# LED_indicators.net
KiCad netlist of a schematic drawn in Altium Designer
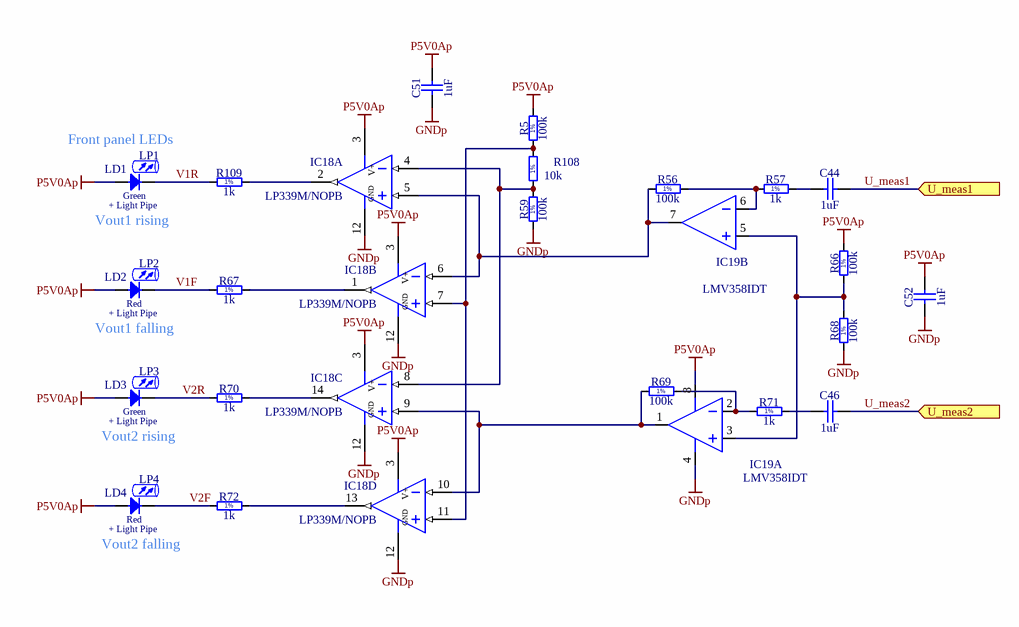
[diagram p0: LED_indicators.SchDoc]

(export (version "E")
  (design (tool "Eeschema 10.0.6"))
  (components
    (comp (ref "C44")
      (value "1uF")
      (footprint "CAPC1005X55N")
      (description "Non-polarised capacitor")
      (fields
        (field (name "PART NUMBER") "CC0402_1UF_16V_10%_X5R")
        (field (name "VOLTAGE") "16V")
        (field (name "AUTHOR") "CERN DEM JLC")
      )
      (libsource (lib "Capacitors") (part "Capacitor - non polarized"))
    )
    (comp (ref "C46")
      (value "1uF")
      (footprint "CAPC1005X55N")
      (description "Non-polarised capacitor")
      (fields
        (field (name "PART NUMBER") "CC0402_1UF_16V_10%_X5R")
        (field (name "VOLTAGE") "16V")
        (field (name "AUTHOR") "CERN DEM JLC")
      )
      (libsource (lib "Capacitors") (part "Capacitor - non polarized"))
    )
    (comp (ref "C51")
      (value "1uF")
      (footprint "CAPC1005X55N")
      (description "Non-polarised capacitor")
      (fields
        (field (name "PART NUMBER") "CC0402_1UF_16V_10%_X5R")
        (field (name "VOLTAGE") "16V")
        (field (name "AUTHOR") "CERN DEM JLC")
      )
      (libsource (lib "Capacitors") (part "Capacitor - non polarized"))
    )
    (comp (ref "C52")
      (value "1uF")
      (footprint "CAPC1005X55N")
      (description "Non-polarised capacitor")
      (fields
        (field (name "PART NUMBER") "CC0402_1UF_16V_10%_X5R")
        (field (name "VOLTAGE") "16V")
        (field (name "AUTHOR") "CERN DEM JLC")
      )
      (libsource (lib "Capacitors") (part "Capacitor - non polarized"))
    )
    (comp (ref "IC18")
      (value "LP339M/NOPB")
      (footprint "SOIC127P600X175-14N")
      (description "Quad Operational Amplifier")
      (fields (field (name "MANUFACTURER") "TEXAS INSTRUMENTS") (field (name "AUTHOR") "CERN DEM MR"))
      (libsource (lib "ICs And Semiconductors") (part "Operational Amplifier x4 Type5"))
    )
    (comp (ref "IC19")
      (value "LMV358IDT")
      (footprint "SO-8")
      (description "Low voltage, Rail-to_Rail output Operational Amplifier")
      (libsource (lib "Amplifiers") (part "OA_LMV358"))
    )
    (comp (ref "LD1")
      (value "Green")
      (footprint "LED_DIALIGHT_555-230")
      (description "LED Green 1C 2A")
      (fields
        (field (name "PART NUMBER") "LED_DIALIGHT_555-2301F")
        (field (name "MANUFACTURER") "DIALIGHT")
        (field (name "AUTHOR") "CERN DEM JMW")
      )
      (libsource (lib "ICs And Semiconductors") (part "LED Green 1C 2A"))
    )
    (comp (ref "LD2")
      (value "Red")
      (footprint "LED_DIALIGHT_555-200")
      (description "LED Red 1C 2A")
      (fields
        (field (name "PART NUMBER") "LED_DIALIGHT_555-2001F")
        (field (name "MANUFACTURER") "DIALIGHT")
        (field (name "AUTHOR") "CERN DEM JMW")
      )
      (libsource (lib "ICs And Semiconductors") (part "LED Red 1C 2A"))
    )
    (comp (ref "LD3")
      (value "Green")
      (footprint "LED_DIALIGHT_555-230")
      (description "LED Green 1C 2A")
      (fields
        (field (name "PART NUMBER") "LED_DIALIGHT_555-2301F")
        (field (name "MANUFACTURER") "DIALIGHT")
        (field (name "AUTHOR") "CERN DEM JMW")
      )
      (libsource (lib "ICs And Semiconductors") (part "LED Green 1C 2A"))
    )
    (comp (ref "LD4")
      (value "Red")
      (footprint "LED_DIALIGHT_555-200")
      (description "LED Red 1C 2A")
      (fields
        (field (name "PART NUMBER") "LED_DIALIGHT_555-2001F")
        (field (name "MANUFACTURER") "DIALIGHT")
        (field (name "AUTHOR") "CERN DEM JMW")
      )
      (libsource (lib "ICs And Semiconductors") (part "LED Red 1C 2A"))
    )
    (comp (ref "LP1")
      (value "~")
      (footprint "LEDLP_BIVAR_PLP2-1200")
      (description "LED Light Pipe x1 Type1")
      (fields
        (field (name "PART NUMBER") "LEDLP_BIVAR_PLP2-1200")
        (field (name "MANUFACTURER") "BIVAR")
        (field (name "AUTHOR") "CERN DEM HF")
      )
      (libsource (lib "ICs And Semiconductors") (part "LED Light Pipe x1 Type1"))
    )
    (comp (ref "LP2")
      (value "~")
      (footprint "LEDLP_BIVAR_PLP2-1200")
      (description "LED Light Pipe x1 Type1")
      (fields
        (field (name "PART NUMBER") "LEDLP_BIVAR_PLP2-1200")
        (field (name "MANUFACTURER") "BIVAR")
        (field (name "AUTHOR") "CERN DEM HF")
      )
      (libsource (lib "ICs And Semiconductors") (part "LED Light Pipe x1 Type1"))
    )
    (comp (ref "LP3")
      (value "~")
      (footprint "LEDLP_BIVAR_PLP2-1200")
      (description "LED Light Pipe x1 Type1")
      (fields
        (field (name "PART NUMBER") "LEDLP_BIVAR_PLP2-1200")
        (field (name "MANUFACTURER") "BIVAR")
        (field (name "AUTHOR") "CERN DEM HF")
      )
      (libsource (lib "ICs And Semiconductors") (part "LED Light Pipe x1 Type1"))
    )
    (comp (ref "LP4")
      (value "~")
      (footprint "LEDLP_BIVAR_PLP2-1200")
      (description "LED Light Pipe x1 Type1")
      (fields
        (field (name "PART NUMBER") "LEDLP_BIVAR_PLP2-1200")
        (field (name "MANUFACTURER") "BIVAR")
        (field (name "AUTHOR") "CERN DEM HF")
      )
      (libsource (lib "ICs And Semiconductors") (part "LED Light Pipe x1 Type1"))
    )
    (comp (ref "R5")
      (value "100k")
      (footprint "RESC1608X55N")
      (description "Resistor - 1%")
      (fields
        (field (name "PART NUMBER") "R0603_100K_1%_0.1W_100PPM")
        (field (name "POWER") "0.1W")
        (field (name "AUTHOR") "CERN DEM JLC")
      )
      (libsource (lib "Resistors") (part "Resistor - 1%"))
    )
    (comp (ref "R56")
      (value "100k")
      (footprint "RESC1608X55N")
      (description "Resistor - 1%")
      (fields
        (field (name "PART NUMBER") "R0603_100K_1%_0.1W_100PPM")
        (field (name "POWER") "0.1W")
        (field (name "AUTHOR") "CERN DEM JLC")
      )
      (libsource (lib "Resistors") (part "Resistor - 1%"))
    )
    (comp (ref "R57")
      (value "1k")
      (footprint "RESC1005X40N")
      (description "Resistor - 1%")
      (fields
        (field (name "PART NUMBER") "R0402_1K_1%_0.0625W_100PPM")
        (field (name "POWER") "0.0625W")
        (field (name "AUTHOR") "CERN DEM JLC")
      )
      (libsource (lib "Resistors") (part "Resistor - 1%"))
    )
    (comp (ref "R59")
      (value "100k")
      (footprint "RESC1608X55N")
      (description "Resistor - 1%")
      (fields
        (field (name "PART NUMBER") "R0603_100K_1%_0.1W_100PPM")
        (field (name "POWER") "0.1W")
        (field (name "AUTHOR") "CERN DEM JLC")
      )
      (libsource (lib "Resistors") (part "Resistor - 1%"))
    )
    (comp (ref "R66")
      (value "100k")
      (footprint "RESC1608X55N")
      (description "Resistor - 1%")
      (fields
        (field (name "PART NUMBER") "R0603_100K_1%_0.1W_100PPM")
        (field (name "POWER") "0.1W")
        (field (name "AUTHOR") "CERN DEM JLC")
      )
      (libsource (lib "Resistors") (part "Resistor - 1%"))
    )
    (comp (ref "R67")
      (value "1k")
      (footprint "RESC1005X40N")
      (description "Resistor - 1%")
      (fields
        (field (name "PART NUMBER") "R0402_1K_1%_0.0625W_100PPM")
        (field (name "POWER") "0.0625W")
        (field (name "AUTHOR") "CERN DEM JLC")
      )
      (libsource (lib "Resistors") (part "Resistor - 1%"))
    )
    (comp (ref "R68")
      (value "100k")
      (footprint "RESC1608X55N")
      (description "Resistor - 1%")
      (fields
        (field (name "PART NUMBER") "R0603_100K_1%_0.1W_100PPM")
        (field (name "POWER") "0.1W")
        (field (name "AUTHOR") "CERN DEM JLC")
      )
      (libsource (lib "Resistors") (part "Resistor - 1%"))
    )
    (comp (ref "R69")
      (value "100k")
      (footprint "RESC1608X55N")
      (description "Resistor - 1%")
      (fields
        (field (name "PART NUMBER") "R0603_100K_1%_0.1W_100PPM")
        (field (name "POWER") "0.1W")
        (field (name "AUTHOR") "CERN DEM JLC")
      )
      (libsource (lib "Resistors") (part "Resistor - 1%"))
    )
    (comp (ref "R70")
      (value "1k")
      (footprint "RESC1005X40N")
      (description "Resistor - 1%")
      (fields
        (field (name "PART NUMBER") "R0402_1K_1%_0.0625W_100PPM")
        (field (name "POWER") "0.0625W")
        (field (name "AUTHOR") "CERN DEM JLC")
      )
      (libsource (lib "Resistors") (part "Resistor - 1%"))
    )
    (comp (ref "R71")
      (value "1k")
      (footprint "RESC1005X40N")
      (description "Resistor - 1%")
      (fields
        (field (name "PART NUMBER") "R0402_1K_1%_0.0625W_100PPM")
        (field (name "POWER") "0.0625W")
        (field (name "AUTHOR") "CERN DEM JLC")
      )
      (libsource (lib "Resistors") (part "Resistor - 1%"))
    )
    (comp (ref "R72")
      (value "1k")
      (footprint "RESC1005X40N")
      (description "Resistor - 1%")
      (fields
        (field (name "PART NUMBER") "R0402_1K_1%_0.0625W_100PPM")
        (field (name "POWER") "0.0625W")
        (field (name "AUTHOR") "CERN DEM JLC")
      )
      (libsource (lib "Resistors") (part "Resistor - 1%"))
    )
    (comp (ref "R108")
      (value "10k")
      (footprint "RESC1005X40N")
      (description "Resistor - 1%")
      (fields
        (field (name "PART NUMBER") "R0402_10K_1%_0.0625W_100PPM")
        (field (name "POWER") "0.0625W")
        (field (name "AUTHOR") "CERN DEM JLC")
      )
      (libsource (lib "Resistors") (part "Resistor - 1%"))
    )
    (comp (ref "R109")
      (value "1k")
      (footprint "RESC1005X40N")
      (description "Resistor - 1%")
      (fields
        (field (name "PART NUMBER") "R0402_1K_1%_0.0625W_100PPM")
        (field (name "POWER") "0.0625W")
        (field (name "AUTHOR") "CERN DEM JLC")
      )
      (libsource (lib "Resistors") (part "Resistor - 1%"))
    )
  )
  (nets
    (net (code "1") (name "/U_meas1") (class "Default")
      (node (ref "C44") (pin "2") (pinfunction "2_2") (pintype "passive"))
    )
    (net (code "2") (name "/U_meas2") (class "Default")
      (node (ref "C46") (pin "2") (pinfunction "2_2") (pintype "passive"))
    )
    (net (code "3") (name "/V1F") (class "Default")
      (node (ref "LD2") (pin "1") (pinfunction "C_1") (pintype "passive"))
      (node (ref "R67") (pin "1") (pinfunction "1_1") (pintype "passive"))
    )
    (net (code "4") (name "/V1R") (class "Default")
      (node (ref "LD1") (pin "1") (pinfunction "C_1") (pintype "passive"))
      (node (ref "R109") (pin "1") (pinfunction "1_1") (pintype "passive"))
    )
    (net (code "5") (name "/V2F") (class "Default")
      (node (ref "LD4") (pin "1") (pinfunction "C_1") (pintype "passive"))
      (node (ref "R72") (pin "1") (pinfunction "1_1") (pintype "passive"))
    )
    (net (code "6") (name "/V2R") (class "Default")
      (node (ref "LD3") (pin "1") (pinfunction "C_1") (pintype "passive"))
      (node (ref "R70") (pin "1") (pinfunction "1_1") (pintype "passive"))
    )
    (net (code "7") (name "GNDp") (class "Default")
      (node (ref "C51") (pin "1") (pinfunction "1_1") (pintype "passive"))
      (node (ref "C52") (pin "1") (pinfunction "1_1") (pintype "passive"))
      (node (ref "IC18") (pin "12") (pinfunction "GND_12") (pintype "power_in"))
      (node (ref "IC19") (pin "4") (pinfunction "V-_4") (pintype "passive"))
      (node (ref "R59") (pin "1") (pinfunction "1_1") (pintype "passive"))
      (node (ref "R68") (pin "1") (pinfunction "1_1") (pintype "passive"))
    )
    (net (code "8") (name "Net-(C44-Pad1)") (class "Default")
      (node (ref "C44") (pin "1") (pinfunction "1_1") (pintype "passive"))
      (node (ref "R57") (pin "2") (pinfunction "2_2") (pintype "passive"))
    )
    (net (code "9") (name "Net-(C46-Pad1)") (class "Default")
      (node (ref "C46") (pin "1") (pinfunction "1_1") (pintype "passive"))
      (node (ref "R71") (pin "2") (pinfunction "2_2") (pintype "passive"))
    )
    (net (code "10") (name "Net-(IC18A-IN+)") (class "Default")
      (node (ref "IC18") (pin "5") (pinfunction "IN+_5") (pintype "input"))
      (node (ref "IC18") (pin "6") (pinfunction "IN-_6") (pintype "input"))
      (node (ref "IC19") (pin "7") (pinfunction "OUT_7") (pintype "passive"))
      (node (ref "R56") (pin "1") (pinfunction "1_1") (pintype "passive"))
    )
    (net (code "11") (name "Net-(IC18A-IN-)") (class "Default")
      (node (ref "IC18") (pin "4") (pinfunction "IN-_4") (pintype "input"))
      (node (ref "IC18") (pin "8") (pinfunction "IN-_8") (pintype "input"))
      (node (ref "R108") (pin "1") (pinfunction "1_1") (pintype "passive"))
      (node (ref "R59") (pin "2") (pinfunction "2_2") (pintype "passive"))
    )
    (net (code "12") (name "Net-(IC18A-OUT)") (class "Default")
      (node (ref "IC18") (pin "2") (pinfunction "OUT_2") (pintype "output"))
      (node (ref "R109") (pin "2") (pinfunction "2_2") (pintype "passive"))
    )
    (net (code "13") (name "Net-(IC18B-IN+)") (class "Default")
      (node (ref "IC18") (pin "11") (pinfunction "IN+_11") (pintype "input"))
      (node (ref "IC18") (pin "7") (pinfunction "IN+_7") (pintype "input"))
      (node (ref "R108") (pin "2") (pinfunction "2_2") (pintype "passive"))
      (node (ref "R5") (pin "1") (pinfunction "1_1") (pintype "passive"))
    )
    (net (code "14") (name "Net-(IC18B-OUT)") (class "Default")
      (node (ref "IC18") (pin "1") (pinfunction "OUT_1") (pintype "output"))
      (node (ref "R67") (pin "2") (pinfunction "2_2") (pintype "passive"))
    )
    (net (code "15") (name "Net-(IC18C-IN+)") (class "Default")
      (node (ref "IC18") (pin "10") (pinfunction "IN-_10") (pintype "input"))
      (node (ref "IC18") (pin "9") (pinfunction "IN+_9") (pintype "input"))
      (node (ref "IC19") (pin "1") (pinfunction "OUT_1") (pintype "passive"))
      (node (ref "R69") (pin "1") (pinfunction "1_1") (pintype "passive"))
    )
    (net (code "16") (name "Net-(IC18C-OUT)") (class "Default")
      (node (ref "IC18") (pin "14") (pinfunction "OUT_14") (pintype "output"))
      (node (ref "R70") (pin "2") (pinfunction "2_2") (pintype "passive"))
    )
    (net (code "17") (name "Net-(IC18D-OUT)") (class "Default")
      (node (ref "IC18") (pin "13") (pinfunction "OUT_13") (pintype "output"))
      (node (ref "R72") (pin "2") (pinfunction "2_2") (pintype "passive"))
    )
    (net (code "18") (name "Net-(IC19A-IN+)") (class "Default")
      (node (ref "IC19") (pin "3") (pinfunction "IN+_3") (pintype "passive"))
      (node (ref "IC19") (pin "5") (pinfunction "IN+_5") (pintype "passive"))
      (node (ref "R66") (pin "1") (pinfunction "1_1") (pintype "passive"))
      (node (ref "R68") (pin "2") (pinfunction "2_2") (pintype "passive"))
    )
    (net (code "19") (name "Net-(IC19A-IN-)") (class "Default")
      (node (ref "IC19") (pin "2") (pinfunction "IN-_2") (pintype "passive"))
      (node (ref "R69") (pin "2") (pinfunction "2_2") (pintype "passive"))
      (node (ref "R71") (pin "1") (pinfunction "1_1") (pintype "passive"))
    )
    (net (code "20") (name "Net-(IC19B-IN-)") (class "Default")
      (node (ref "IC19") (pin "6") (pinfunction "IN-_6") (pintype "passive"))
      (node (ref "R56") (pin "2") (pinfunction "2_2") (pintype "passive"))
      (node (ref "R57") (pin "1") (pinfunction "1_1") (pintype "passive"))
    )
    (net (code "21") (name "P5V0Ap") (class "Default")
      (node (ref "C51") (pin "2") (pinfunction "2_2") (pintype "passive"))
      (node (ref "C52") (pin "2") (pinfunction "2_2") (pintype "passive"))
      (node (ref "IC18") (pin "3") (pinfunction "V+_3") (pintype "power_in"))
      (node (ref "IC19") (pin "8") (pinfunction "V+_8") (pintype "passive"))
      (node (ref "LD1") (pin "2") (pinfunction "A_2") (pintype "passive"))
      (node (ref "LD2") (pin "2") (pinfunction "A_2") (pintype "passive"))
      (node (ref "LD3") (pin "2") (pinfunction "A_2") (pintype "passive"))
      (node (ref "LD4") (pin "2") (pinfunction "A_2") (pintype "passive"))
      (node (ref "R5") (pin "2") (pinfunction "2_2") (pintype "passive"))
      (node (ref "R66") (pin "2") (pinfunction "2_2") (pintype "passive"))
    )
  )
)
